# USB-2-RTMI.net
KiCad netlist of a schematic drawn in Altium Designer
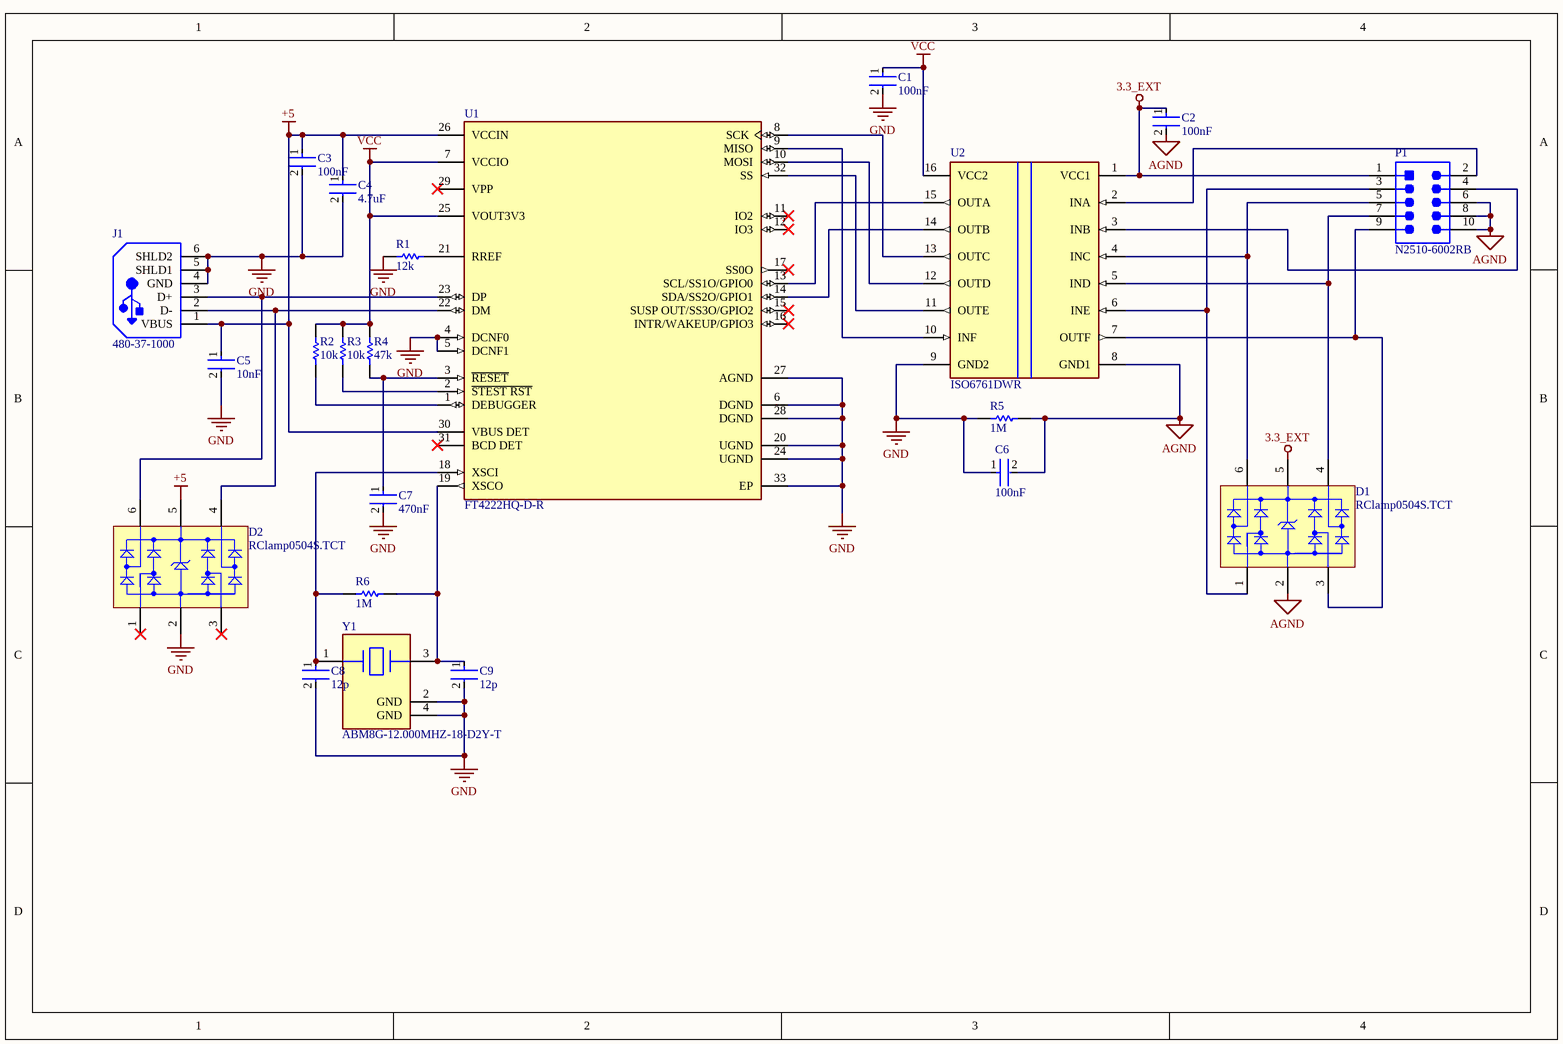
[diagram p0: USB-2-RTMI.SchDoc]

(export (version "E")
  (design (tool "Eeschema 10.0.6"))
  (components
    (comp (ref "C1")
      (value "100nF")
      (footprint "FP-C0805C-DN-MFG")
      (description "CAP CER 0.1UF 50V X7R 0805")
      (fields
        (field (name "MANUFACTURER PART NUMBER") "C0805C104K5RACTU")
        (field (name "MANUFACTURER") "KEMET")
      )
      (libsource (lib "Altium Content Vault") (part "b4654b650e69147ec39a6b967a45e02"))
    )
    (comp (ref "C2")
      (value "100nF")
      (footprint "FP-C0805C-DN-MFG")
      (description "CAP CER 0.1UF 50V X7R 0805")
      (fields
        (field (name "MANUFACTURER PART NUMBER") "C0805C104K5RACTU")
        (field (name "MANUFACTURER") "KEMET")
      )
      (libsource (lib "Altium Content Vault") (part "b4654b650e69147ec39a6b967a45e02"))
    )
    (comp (ref "C3")
      (value "100nF")
      (footprint "FP-C0805C-DN-MFG")
      (description "CAP CER 0.1UF 50V X7R 0805")
      (fields
        (field (name "MANUFACTURER PART NUMBER") "C0805C104K5RACTU")
        (field (name "MANUFACTURER") "KEMET")
      )
      (libsource (lib "Altium Content Vault") (part "b4654b650e69147ec39a6b967a45e02"))
    )
    (comp (ref "C4")
      (value "4.7uF")
      (footprint "FP-C0805C-DN-MFG")
      (description "CAP CER 0.1UF 50V X7R 0805")
      (fields
        (field (name "MANUFACTURER PART NUMBER") "C0805C104K5RACTU")
        (field (name "MANUFACTURER") "KEMET")
      )
      (libsource (lib "Altium Content Vault") (part "b4654b650e69147ec39a6b967a45e02"))
    )
    (comp (ref "C5")
      (value "10nF")
      (footprint "FP-C0805C-DN-MFG")
      (description "CAP CER 0.1UF 50V X7R 0805")
      (fields
        (field (name "MANUFACTURER PART NUMBER") "C0805C104K5RACTU")
        (field (name "MANUFACTURER") "KEMET")
      )
      (libsource (lib "Altium Content Vault") (part "b4654b650e69147ec39a6b967a45e02"))
    )
    (comp (ref "C6")
      (value "100nF")
      (footprint "FP-C0805C-DN-MFG")
      (description "CAP CER 0.1UF 50V X7R 0805")
      (fields
        (field (name "MANUFACTURER PART NUMBER") "C0805C104K5RACTU")
        (field (name "MANUFACTURER") "KEMET")
      )
      (libsource (lib "Altium Content Vault") (part "b4654b650e69147ec39a6b967a45e02"))
    )
    (comp (ref "C7")
      (value "470nF")
      (footprint "FP-C0805C-DN-MFG")
      (description "CAP CER 0.1UF 50V X7R 0805")
      (fields
        (field (name "MANUFACTURER PART NUMBER") "C0805C104K5RACTU")
        (field (name "MANUFACTURER") "KEMET")
      )
      (libsource (lib "Altium Content Vault") (part "b4654b650e69147ec39a6b967a45e02"))
    )
    (comp (ref "C8")
      (value "12p")
      (footprint "FP-C0805C-DN-MFG")
      (description "CAP CER 0.1UF 50V X7R 0805")
      (fields
        (field (name "MANUFACTURER PART NUMBER") "C0805C104K5RACTU")
        (field (name "MANUFACTURER") "KEMET")
      )
      (libsource (lib "Altium Content Vault") (part "b4654b650e69147ec39a6b967a45e02"))
    )
    (comp (ref "C9")
      (value "12p")
      (footprint "FP-C0805C-DN-MFG")
      (description "CAP CER 0.1UF 50V X7R 0805")
      (fields
        (field (name "MANUFACTURER PART NUMBER") "C0805C104K5RACTU")
        (field (name "MANUFACTURER") "KEMET")
      )
      (libsource (lib "Altium Content Vault") (part "b4654b650e69147ec39a6b967a45e02"))
    )
    (comp (ref "D1")
      (value "RClamp0504S.TCT")
      (footprint "SEMT-SOT-23-6_V")
      (description "RailClamp@ Low Capacitance TVS Array, 5 V VRWM, -55 to 125 degC, 6-Pin SOT-23, RoHS, Tape and Reel")
      (fields (field (name "MANUFACTURER") "Semtech"))
      (libsource (lib "Altium Content Vault") (part "SEMT-RCLAMP0504S-SOT-23-6"))
    )
    (comp (ref "D2")
      (value "RClamp0504S.TCT")
      (footprint "SEMT-SOT-23-6_V")
      (description "RailClamp@ Low Capacitance TVS Array, 5 V VRWM, -55 to 125 degC, 6-Pin SOT-23, RoHS, Tape and Reel")
      (fields (field (name "MANUFACTURER") "Semtech"))
      (libsource (lib "Altium Content Vault") (part "SEMT-RCLAMP0504S-SOT-23-6"))
    )
    (comp (ref "J1")
      (value "480-37-1000")
      (footprint "MOLX-480-37-1000_V")
      (fields (field (name "TOLERANCE") "1%"))
      (libsource (lib "Altium Content Vault") (part "USB-4-2SHLD"))
    )
    (comp (ref "P1")
      (value "N2510-6002RB")
      (footprint "3M-N2510-6002-10_V")
      (fields (field (name "PARTNUMBER") "N2510") (field (name "MANUFACTURER") "3M"))
      (libsource (lib "Altium Content Vault") (part "CN-2P-M-R10"))
    )
    (comp (ref "R1")
      (value "12k")
      (footprint "RESC2013X60X35NL10T20")
      (description "Chip Resistor, 10 KOhm, +/- 1%, 0.125 W, -55 to 155 degC, 0805 (2012 Metric), RoHS, Tape and Reel")
      (fields (field (name "MANUFACTURER") "Yageo"))
      (libsource (lib "Altium Content Vault") (part "RES-2"))
    )
    (comp (ref "R2")
      (value "10k")
      (footprint "RESC2013X60X35NL10T20")
      (description "Chip Resistor, 10 KOhm, +/- 1%, 0.125 W, -55 to 155 degC, 0805 (2012 Metric), RoHS, Tape and Reel")
      (fields (field (name "MANUFACTURER") "Yageo"))
      (libsource (lib "Altium Content Vault") (part "RES-2"))
    )
    (comp (ref "R3")
      (value "10k")
      (footprint "RESC2013X60X35NL10T20")
      (description "Chip Resistor, 10 KOhm, +/- 1%, 0.125 W, -55 to 155 degC, 0805 (2012 Metric), RoHS, Tape and Reel")
      (fields (field (name "MANUFACTURER") "Yageo"))
      (libsource (lib "Altium Content Vault") (part "RES-2"))
    )
    (comp (ref "R4")
      (value "47k")
      (footprint "RESC2013X60X35NL10T20")
      (description "Chip Resistor, 10 KOhm, +/- 1%, 0.125 W, -55 to 155 degC, 0805 (2012 Metric), RoHS, Tape and Reel")
      (fields (field (name "MANUFACTURER") "Yageo"))
      (libsource (lib "Altium Content Vault") (part "RES-2"))
    )
    (comp (ref "R5")
      (value "1M")
      (footprint "RESC2013X60X35NL10T20")
      (description "Chip Resistor, 10 KOhm, +/- 1%, 0.125 W, -55 to 155 degC, 0805 (2012 Metric), RoHS, Tape and Reel")
      (fields (field (name "MANUFACTURER") "Yageo"))
      (libsource (lib "Altium Content Vault") (part "RES-2"))
    )
    (comp (ref "R6")
      (value "1M")
      (footprint "RESC2013X60X35NL10T20")
      (description "Chip Resistor, 10 KOhm, +/- 1%, 0.125 W, -55 to 155 degC, 0805 (2012 Metric), RoHS, Tape and Reel")
      (fields (field (name "MANUFACTURER") "Yageo"))
      (libsource (lib "Altium Content Vault") (part "RES-2"))
    )
    (comp (ref "U1")
      (value "FT4222HQ-D-R")
      (footprint "FP-VQFN-32-MFG")
      (description "IC BRIDGE USB TO I2C/SPI 32VQFN")
      (libsource (lib "Altium Content Vault") (part "7b9cc2f54295c9c30444f8926824a7a"))
    )
    (comp (ref "U2")
      (value "ISO6761DWR")
      (footprint "FP-DW0016A-IPC_B")
      (description "GENERAL PURPOSE, 50-MBPS, SIX-CH")
      (libsource (lib "Altium Content Vault") (part "50ae8ad16c2fb7a32efe3143e4095fa"))
    )
    (comp (ref "Y1")
      (value "ABM8G-12.000MHZ-18-D2Y-T")
      (footprint "FP-ABM8G-MFG")
      (description "Crystal 12MHz ±20ppm (Tol) ±30ppm (Stability) 18pF FUND 120Ω 4-Pin SMD T/R")
      (fields (field (name "TOLERANCE") "20ppm"))
      (libsource (lib "Altium Content Vault") (part "48e526d86b7f2615d98721063c72f49"))
    )
  )
  (nets
    (net (code "1") (name "+5") (class "Default")
      (node (ref "C3") (pin "1") (pinfunction "1_1") (pintype "passive"))
      (node (ref "C4") (pin "1") (pinfunction "1_1") (pintype "passive"))
      (node (ref "C5") (pin "1") (pinfunction "1_1") (pintype "passive"))
      (node (ref "D2") (pin "5") (pinfunction "VCC/NC_5") (pintype "passive"))
      (node (ref "J1") (pin "1") (pinfunction "VBUS_1") (pintype "passive"))
      (node (ref "U1") (pin "26") (pinfunction "VCCIN_26") (pintype "power_in"))
      (node (ref "U1") (pin "30") (pinfunction "VBUS_DET_30") (pintype "power_in"))
    )
    (net (code "2") (name "3.3_EXT") (class "Default")
      (node (ref "C2") (pin "1") (pinfunction "1_1") (pintype "passive"))
      (node (ref "D1") (pin "5") (pinfunction "VCC/NC_5") (pintype "passive"))
      (node (ref "P1") (pin "1") (pinfunction "1_1") (pintype "passive"))
      (node (ref "U2") (pin "1") (pinfunction "VCC1_1") (pintype "power_in"))
    )
    (net (code "3") (name "AGND") (class "Default")
      (node (ref "C2") (pin "2") (pinfunction "2_2") (pintype "passive"))
      (node (ref "C6") (pin "2") (pinfunction "2_2") (pintype "passive"))
      (node (ref "D1") (pin "2") (pinfunction "GND_2") (pintype "power_in"))
      (node (ref "P1") (pin "10") (pinfunction "10_10") (pintype "passive"))
      (node (ref "P1") (pin "6") (pinfunction "6_6") (pintype "passive"))
      (node (ref "P1") (pin "8") (pinfunction "8_8") (pintype "passive"))
      (node (ref "R5") (pin "2") (pinfunction "2_2") (pintype "passive"))
      (node (ref "U2") (pin "8") (pinfunction "GND1_8") (pintype "passive"))
    )
    (net (code "4") (name "GND") (class "Default")
      (node (ref "C1") (pin "2") (pinfunction "2_2") (pintype "passive"))
      (node (ref "C3") (pin "2") (pinfunction "2_2") (pintype "passive"))
      (node (ref "C4") (pin "2") (pinfunction "2_2") (pintype "passive"))
      (node (ref "C5") (pin "2") (pinfunction "2_2") (pintype "passive"))
      (node (ref "C6") (pin "1") (pinfunction "1_1") (pintype "passive"))
      (node (ref "C7") (pin "2") (pinfunction "2_2") (pintype "passive"))
      (node (ref "C8") (pin "2") (pinfunction "2_2") (pintype "passive"))
      (node (ref "C9") (pin "2") (pinfunction "2_2") (pintype "passive"))
      (node (ref "D2") (pin "2") (pinfunction "GND_2") (pintype "power_in"))
      (node (ref "J1") (pin "4") (pinfunction "GND_4") (pintype "passive"))
      (node (ref "J1") (pin "5") (pinfunction "SHLD1_5") (pintype "passive"))
      (node (ref "J1") (pin "6") (pinfunction "SHLD2_6") (pintype "passive"))
      (node (ref "R1") (pin "1") (pinfunction "1_1") (pintype "passive"))
      (node (ref "R5") (pin "1") (pinfunction "1_1") (pintype "passive"))
      (node (ref "U1") (pin "20") (pinfunction "UGND_20") (pintype "power_in"))
      (node (ref "U1") (pin "24") (pinfunction "UGND_24") (pintype "power_in"))
      (node (ref "U1") (pin "27") (pinfunction "AGND_27") (pintype "power_in"))
      (node (ref "U1") (pin "28") (pinfunction "DGND_28") (pintype "power_in"))
      (node (ref "U1") (pin "33") (pinfunction "EP_33") (pintype "passive"))
      (node (ref "U1") (pin "4") (pinfunction "DCNF0_4") (pintype "input"))
      (node (ref "U1") (pin "5") (pinfunction "DCNF1_5") (pintype "input"))
      (node (ref "U1") (pin "6") (pinfunction "DGND_6") (pintype "power_in"))
      (node (ref "U2") (pin "9") (pinfunction "GND2_9") (pintype "power_in"))
      (node (ref "Y1") (pin "2") (pinfunction "GND_2") (pintype "power_in"))
      (node (ref "Y1") (pin "4") (pinfunction "GND_4") (pintype "power_in"))
    )
    (net (code "5") (name "Net-(D1-I{slash}O_1)") (class "Default")
      (node (ref "D1") (pin "1") (pinfunction "I/O_1_1") (pintype "passive"))
      (node (ref "P1") (pin "3") (pinfunction "3_3") (pintype "passive"))
      (node (ref "U2") (pin "6") (pinfunction "INE_6") (pintype "input"))
    )
    (net (code "6") (name "Net-(D1-I{slash}O_2)") (class "Default")
      (node (ref "D1") (pin "6") (pinfunction "I/O_2_6") (pintype "passive"))
      (node (ref "P1") (pin "5") (pinfunction "5_5") (pintype "passive"))
      (node (ref "U2") (pin "4") (pinfunction "INC_4") (pintype "input"))
    )
    (net (code "7") (name "Net-(D1-I{slash}O_3)") (class "Default")
      (node (ref "D1") (pin "3") (pinfunction "I/O_3_3") (pintype "passive"))
      (node (ref "P1") (pin "9") (pinfunction "9_9") (pintype "passive"))
      (node (ref "U2") (pin "7") (pinfunction "OUTF_7") (pintype "output"))
    )
    (net (code "8") (name "Net-(D1-I{slash}O_4)") (class "Default")
      (node (ref "D1") (pin "4") (pinfunction "I/O_4_4") (pintype "passive"))
      (node (ref "P1") (pin "7") (pinfunction "7_7") (pintype "passive"))
      (node (ref "U2") (pin "5") (pinfunction "IND_5") (pintype "input"))
    )
    (net (code "9") (name "Net-(D2-I{slash}O_2)") (class "Default")
      (node (ref "D2") (pin "6") (pinfunction "I/O_2_6") (pintype "passive"))
      (node (ref "J1") (pin "3") (pinfunction "D+_3") (pintype "passive"))
      (node (ref "U1") (pin "23") (pinfunction "DP_23") (pintype "bidirectional"))
    )
    (net (code "10") (name "Net-(D2-I{slash}O_4)") (class "Default")
      (node (ref "D2") (pin "4") (pinfunction "I/O_4_4") (pintype "passive"))
      (node (ref "J1") (pin "2") (pinfunction "D-_2") (pintype "passive"))
      (node (ref "U1") (pin "22") (pinfunction "DM_22") (pintype "bidirectional"))
    )
    (net (code "11") (name "Net-(U1-DEBUGGER)") (class "Default")
      (node (ref "R2") (pin "1") (pinfunction "1_1") (pintype "passive"))
      (node (ref "U1") (pin "1") (pinfunction "DEBUGGER_1") (pintype "bidirectional"))
    )
    (net (code "12") (name "Net-(U1-MISO)") (class "Default")
      (node (ref "U1") (pin "9") (pinfunction "MISO_9") (pintype "bidirectional"))
      (node (ref "U2") (pin "10") (pinfunction "INF_10") (pintype "input"))
    )
    (net (code "13") (name "Net-(U1-MOSI)") (class "Default")
      (node (ref "U1") (pin "10") (pinfunction "MOSI_10") (pintype "bidirectional"))
      (node (ref "U2") (pin "12") (pinfunction "OUTD_12") (pintype "output"))
    )
    (net (code "14") (name "Net-(U1-RREF)") (class "Default")
      (node (ref "R1") (pin "2") (pinfunction "2_2") (pintype "passive"))
      (node (ref "U1") (pin "21") (pinfunction "RREF_21") (pintype "passive"))
    )
    (net (code "15") (name "Net-(U1-SCK)") (class "Default")
      (node (ref "U1") (pin "8") (pinfunction "SCK_8") (pintype "bidirectional"))
      (node (ref "U2") (pin "13") (pinfunction "OUTC_13") (pintype "output"))
    )
    (net (code "16") (name "Net-(U1-SCL{slash}SS1O{slash}GPIO0)") (class "Default")
      (node (ref "U1") (pin "13") (pinfunction "SCL/SS1O/GPIO0_13") (pintype "bidirectional"))
      (node (ref "U2") (pin "15") (pinfunction "OUTA_15") (pintype "output"))
    )
    (net (code "17") (name "Net-(U1-SDA{slash}SS2O{slash}GPIO1)") (class "Default")
      (node (ref "U1") (pin "14") (pinfunction "SDA/SS2O/GPIO1_14") (pintype "bidirectional"))
      (node (ref "U2") (pin "14") (pinfunction "OUTB_14") (pintype "output"))
    )
    (net (code "18") (name "Net-(U1-SS)") (class "Default")
      (node (ref "U1") (pin "32") (pinfunction "SS_32") (pintype "input"))
      (node (ref "U2") (pin "11") (pinfunction "OUTE_11") (pintype "output"))
    )
    (net (code "19") (name "Net-(U1-XSCI)") (class "Default")
      (node (ref "C8") (pin "1") (pinfunction "1_1") (pintype "passive"))
      (node (ref "R6") (pin "1") (pinfunction "1_1") (pintype "passive"))
      (node (ref "U1") (pin "18") (pinfunction "XSCI_18") (pintype "input"))
      (node (ref "Y1") (pin "1") (pinfunction "1_1") (pintype "passive"))
    )
    (net (code "20") (name "Net-(U1-XSCO)") (class "Default")
      (node (ref "C9") (pin "1") (pinfunction "1_1") (pintype "passive"))
      (node (ref "R6") (pin "2") (pinfunction "2_2") (pintype "passive"))
      (node (ref "U1") (pin "19") (pinfunction "XSCO_19") (pintype "output"))
      (node (ref "Y1") (pin "3") (pinfunction "3_3") (pintype "passive"))
    )
    (net (code "21") (name "Net-(U1-~{RESET})") (class "Default")
      (node (ref "C7") (pin "1") (pinfunction "1_1") (pintype "passive"))
      (node (ref "R4") (pin "1") (pinfunction "1_1") (pintype "passive"))
      (node (ref "U1") (pin "3") (pinfunction "~{RESET}_3") (pintype "input"))
    )
    (net (code "22") (name "Net-(U1-~{STEST_RST})") (class "Default")
      (node (ref "R3") (pin "1") (pinfunction "1_1") (pintype "passive"))
      (node (ref "U1") (pin "2") (pinfunction "~{STEST_RST}_2") (pintype "input"))
    )
    (net (code "23") (name "Net-(U2-INA)") (class "Default")
      (node (ref "P1") (pin "2") (pinfunction "2_2") (pintype "passive"))
      (node (ref "U2") (pin "2") (pinfunction "INA_2") (pintype "input"))
    )
    (net (code "24") (name "Net-(U2-INB)") (class "Default")
      (node (ref "P1") (pin "4") (pinfunction "4_4") (pintype "passive"))
      (node (ref "U2") (pin "3") (pinfunction "INB_3") (pintype "input"))
    )
    (net (code "25") (name "VCC") (class "Default")
      (node (ref "C1") (pin "1") (pinfunction "1_1") (pintype "passive"))
      (node (ref "R2") (pin "2") (pinfunction "2_2") (pintype "passive"))
      (node (ref "R3") (pin "2") (pinfunction "2_2") (pintype "passive"))
      (node (ref "R4") (pin "2") (pinfunction "2_2") (pintype "passive"))
      (node (ref "U1") (pin "25") (pinfunction "VOUT3V3_25") (pintype "power_in"))
      (node (ref "U1") (pin "7") (pinfunction "VCCIO_7") (pintype "power_in"))
      (node (ref "U2") (pin "16") (pinfunction "VCC2_16") (pintype "power_in"))
    )
    (net (code "26") (name "unconnected-(D2-I{slash}O_1-Pad1)") (class "Default")
      (node (ref "D2") (pin "1") (pinfunction "I/O_1_1") (pintype "passive+no_connect"))
    )
    (net (code "27") (name "unconnected-(D2-I{slash}O_3-Pad3)") (class "Default")
      (node (ref "D2") (pin "3") (pinfunction "I/O_3_3") (pintype "passive+no_connect"))
    )
    (net (code "28") (name "unconnected-(U1-BCD_DET-Pad31)") (class "Default")
      (node (ref "U1") (pin "31") (pinfunction "BCD_DET_31") (pintype "passive+no_connect"))
    )
    (net (code "29") (name "unconnected-(U1-INTR{slash}WAKEUP{slash}GPIO3-Pad16)") (class "Default")
      (node (ref "U1") (pin "16") (pinfunction "INTR/WAKEUP/GPIO3_16") (pintype "bidirectional+no_connect"))
    )
    (net (code "30") (name "unconnected-(U1-IO2-Pad11)") (class "Default")
      (node (ref "U1") (pin "11") (pinfunction "IO2_11") (pintype "bidirectional+no_connect"))
    )
    (net (code "31") (name "unconnected-(U1-IO3-Pad12)") (class "Default")
      (node (ref "U1") (pin "12") (pinfunction "IO3_12") (pintype "bidirectional+no_connect"))
    )
    (net (code "32") (name "unconnected-(U1-SS0O-Pad17)") (class "Default")
      (node (ref "U1") (pin "17") (pinfunction "SS0O_17") (pintype "output+no_connect"))
    )
    (net (code "33") (name "unconnected-(U1-SUSP_OUT{slash}SS3O{slash}GPIO2-Pad15)") (class "Default")
      (node (ref "U1") (pin "15") (pinfunction "SUSP_OUT/SS3O/GPIO2_15") (pintype "bidirectional+no_connect"))
    )
    (net (code "34") (name "unconnected-(U1-VPP-Pad29)") (class "Default")
      (node (ref "U1") (pin "29") (pinfunction "VPP_29") (pintype "power_in+no_connect"))
    )
  )
)
